# final.net
KiCad netlist of a schematic drawn in EAGLE
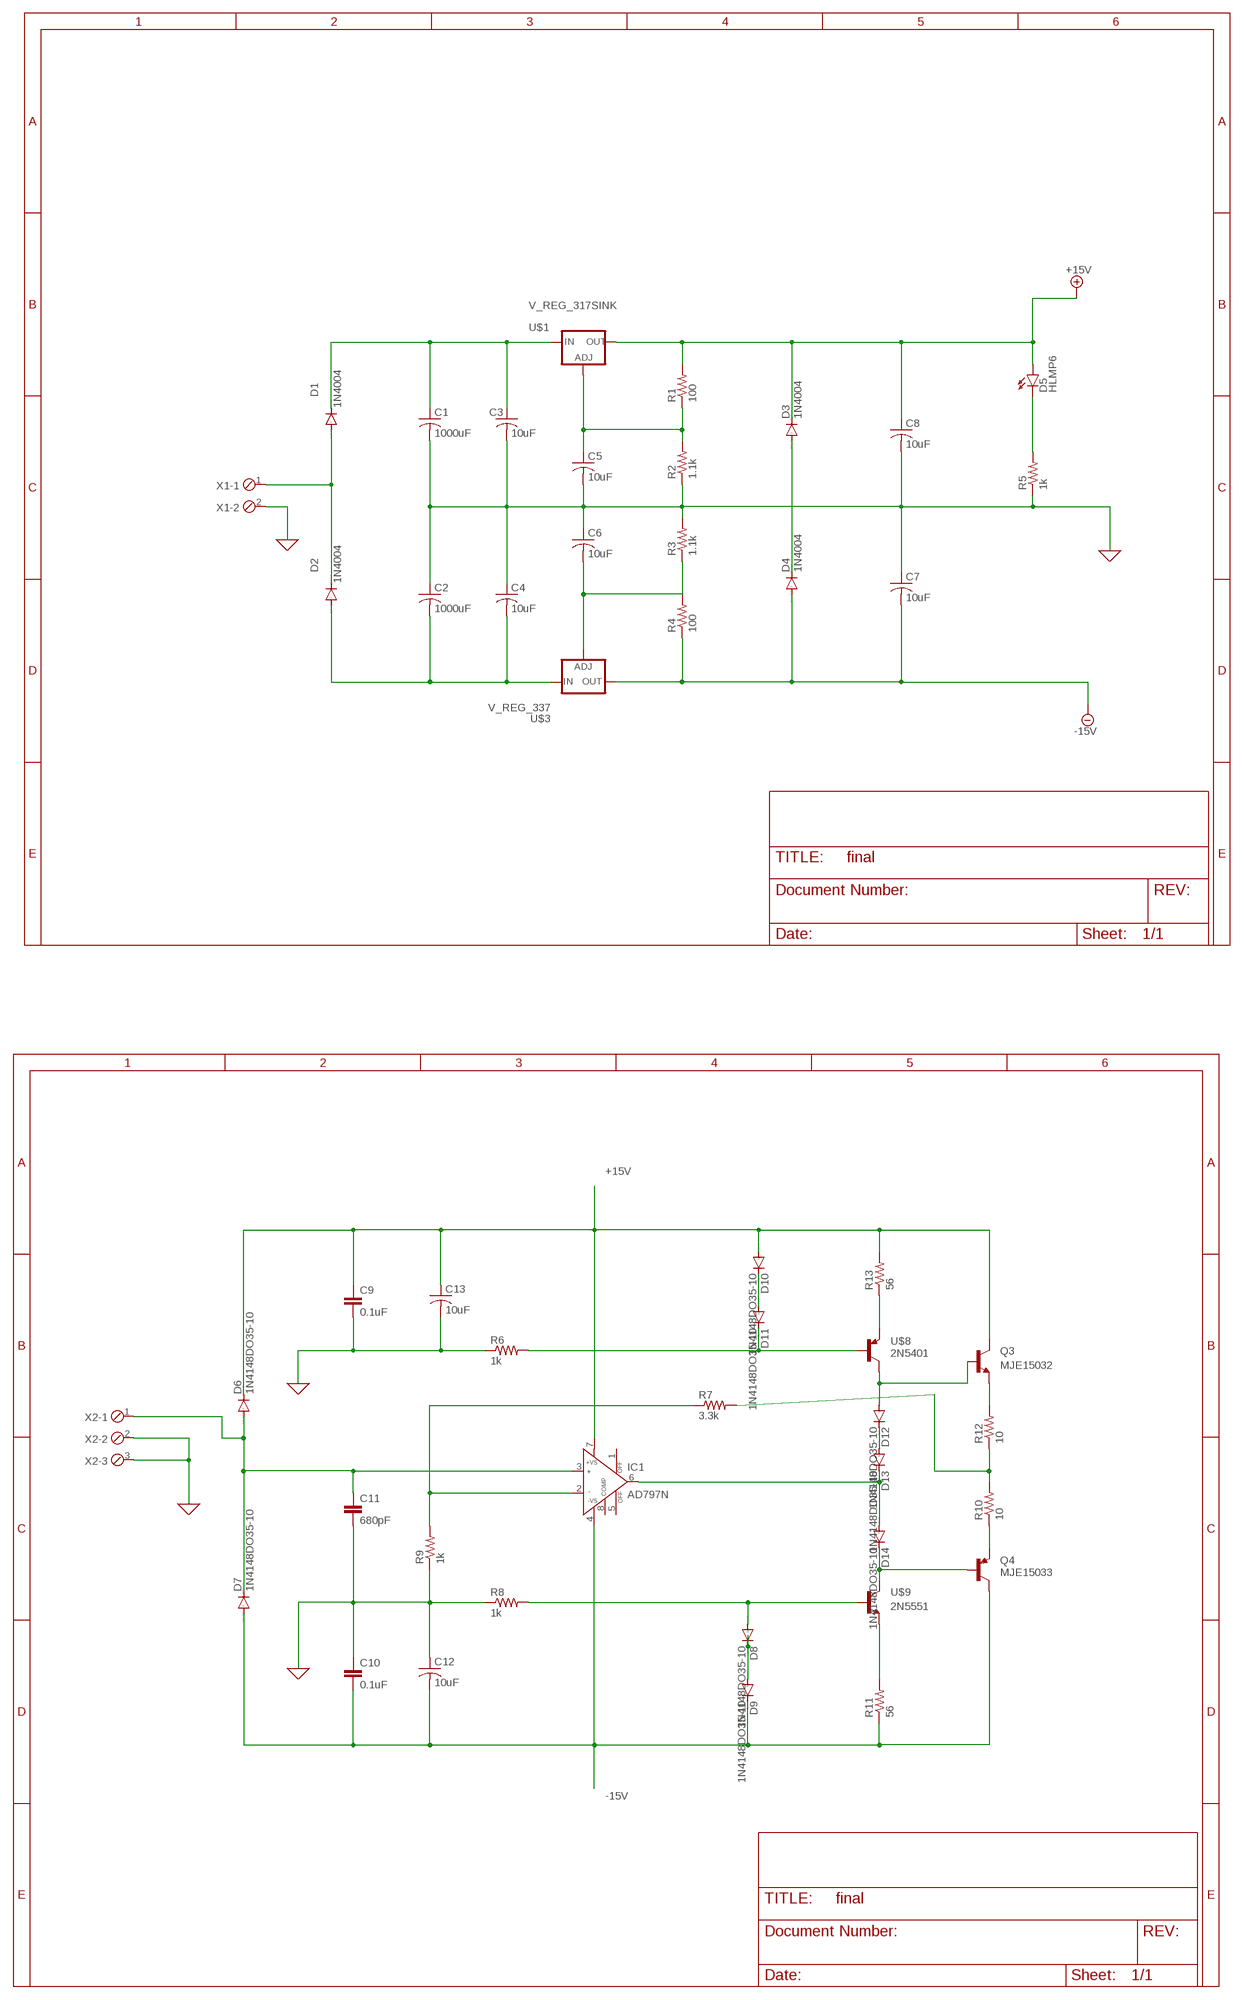
[diagram p0: schematic, sheet 1, part 1 of 2]
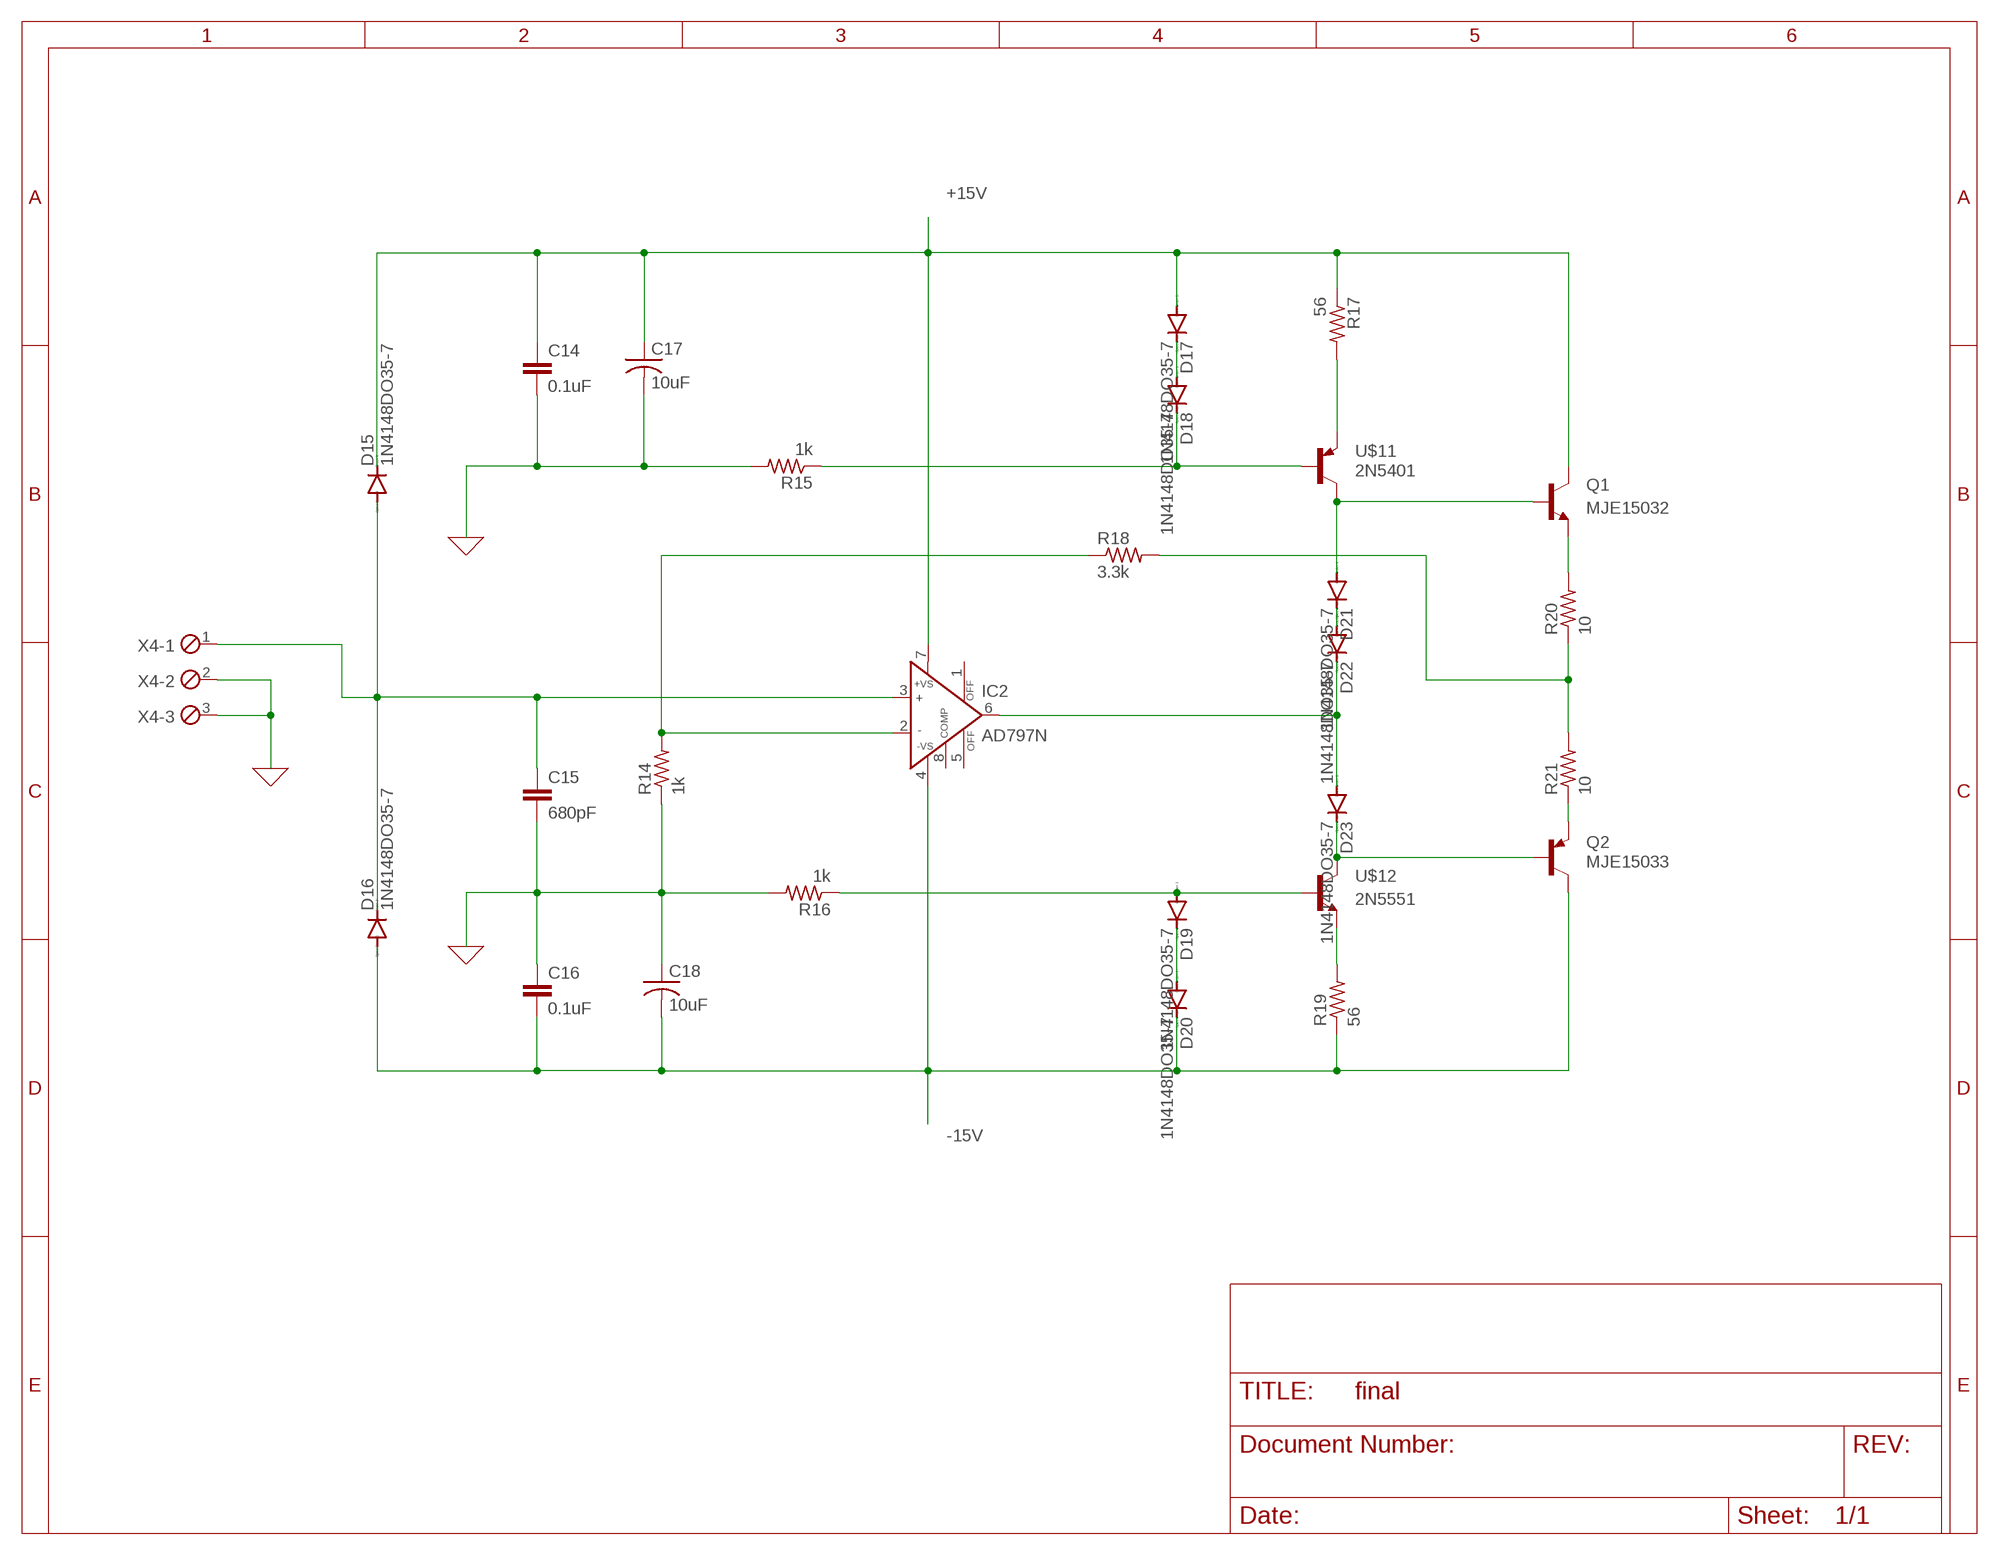
[diagram p1: schematic, sheet 1, part 2 of 2]

(export (version "E")
  (design (tool "Eeschema 10.0.6"))
  (components
    (comp (ref "C1")
      (value "1000uF")
      (footprint "eagle-import:C050-024X044")
      (libsource (lib "eagle-import") (part "C-US050-024X044"))
    )
    (comp (ref "C2")
      (value "1000uF")
      (footprint "eagle-import:C050-024X044")
      (libsource (lib "eagle-import") (part "C-US050-024X044"))
    )
    (comp (ref "C3")
      (value "10uF")
      (footprint "eagle-import:C050-024X044")
      (libsource (lib "eagle-import") (part "C-US050-024X044"))
    )
    (comp (ref "C4")
      (value "10uF")
      (footprint "eagle-import:C050-024X044")
      (libsource (lib "eagle-import") (part "C-US050-024X044"))
    )
    (comp (ref "C5")
      (value "10uF")
      (footprint "eagle-import:C050-024X044")
      (libsource (lib "eagle-import") (part "C-US050-024X044"))
    )
    (comp (ref "C6")
      (value "10uF")
      (footprint "eagle-import:C050-024X044")
      (libsource (lib "eagle-import") (part "C-US050-024X044"))
    )
    (comp (ref "C7")
      (value "10uF")
      (footprint "eagle-import:C050-024X044")
      (libsource (lib "eagle-import") (part "C-US050-024X044"))
    )
    (comp (ref "C8")
      (value "10uF")
      (footprint "eagle-import:C050-024X044")
      (libsource (lib "eagle-import") (part "C-US050-024X044"))
    )
    (comp (ref "C9")
      (value "0.1uF")
      (footprint "eagle-import:C2.5-3")
      (libsource (lib "eagle-import") (part "C2,5-3"))
    )
    (comp (ref "C10")
      (value "0.1uF")
      (footprint "eagle-import:C2.5-3")
      (libsource (lib "eagle-import") (part "C2,5-3"))
    )
    (comp (ref "C11")
      (value "680pF")
      (footprint "eagle-import:C2.5-3")
      (libsource (lib "eagle-import") (part "C2,5-3"))
    )
    (comp (ref "C12")
      (value "10uF")
      (footprint "eagle-import:C050-024X044")
      (libsource (lib "eagle-import") (part "C-US050-024X044"))
    )
    (comp (ref "C13")
      (value "10uF")
      (footprint "eagle-import:C050-024X044")
      (libsource (lib "eagle-import") (part "C-US050-024X044"))
    )
    (comp (ref "C14")
      (value "0.1uF")
      (footprint "eagle-import:C2.5-3")
      (libsource (lib "eagle-import") (part "C2,5-3"))
    )
    (comp (ref "C15")
      (value "680pF")
      (footprint "eagle-import:C2.5-3")
      (libsource (lib "eagle-import") (part "C2,5-3"))
    )
    (comp (ref "C16")
      (value "0.1uF")
      (footprint "eagle-import:C2.5-3")
      (libsource (lib "eagle-import") (part "C2,5-3"))
    )
    (comp (ref "C17")
      (value "10uF")
      (footprint "eagle-import:C050-024X044")
      (libsource (lib "eagle-import") (part "C-US050-024X044"))
    )
    (comp (ref "C18")
      (value "10uF")
      (footprint "eagle-import:C050-024X044")
      (libsource (lib "eagle-import") (part "C-US050-024X044"))
    )
    (comp (ref "D1")
      (value "1N4004")
      (footprint "eagle-import:DO41-10")
      (libsource (lib "eagle-import") (part "1N4004"))
    )
    (comp (ref "D2")
      (value "1N4004")
      (footprint "eagle-import:DO41-10")
      (libsource (lib "eagle-import") (part "1N4004"))
    )
    (comp (ref "D3")
      (value "1N4004")
      (footprint "eagle-import:DO41-10")
      (libsource (lib "eagle-import") (part "1N4004"))
    )
    (comp (ref "D4")
      (value "1N4004")
      (footprint "eagle-import:DO41-10")
      (libsource (lib "eagle-import") (part "1N4004"))
    )
    (comp (ref "D5")
      (value "HLMP6")
      (footprint "eagle-import:HLMP6")
      (fields (field (name "MF") "AGILENT TECHNOLOGIES") (field (name "MPN") "HLMP-6500"))
      (libsource (lib "eagle-import") (part "HLMP6"))
    )
    (comp (ref "D6")
      (value "1N4148DO35-10")
      (footprint "eagle-import:DO35-10")
      (libsource (lib "eagle-import") (part "1N4148DO35-10"))
    )
    (comp (ref "D7")
      (value "1N4148DO35-10")
      (footprint "eagle-import:DO35-10")
      (libsource (lib "eagle-import") (part "1N4148DO35-10"))
    )
    (comp (ref "D8")
      (value "1N4148DO35-10")
      (footprint "eagle-import:DO35-10")
      (libsource (lib "eagle-import") (part "1N4148DO35-10"))
    )
    (comp (ref "D9")
      (value "1N4148DO35-10")
      (footprint "eagle-import:DO35-10")
      (libsource (lib "eagle-import") (part "1N4148DO35-10"))
    )
    (comp (ref "D10")
      (value "1N4148DO35-10")
      (footprint "eagle-import:DO35-10")
      (libsource (lib "eagle-import") (part "1N4148DO35-10"))
    )
    (comp (ref "D11")
      (value "1N4148DO35-10")
      (footprint "eagle-import:DO35-10")
      (libsource (lib "eagle-import") (part "1N4148DO35-10"))
    )
    (comp (ref "D12")
      (value "1N4148DO35-10")
      (footprint "eagle-import:DO35-10")
      (libsource (lib "eagle-import") (part "1N4148DO35-10"))
    )
    (comp (ref "D13")
      (value "1N4148DO35-10")
      (footprint "eagle-import:DO35-10")
      (libsource (lib "eagle-import") (part "1N4148DO35-10"))
    )
    (comp (ref "D14")
      (value "1N4148DO35-10")
      (footprint "eagle-import:DO35-10")
      (libsource (lib "eagle-import") (part "1N4148DO35-10"))
    )
    (comp (ref "D15")
      (value "1N4148DO35-7")
      (footprint "eagle-import:DO35-7")
      (libsource (lib "eagle-import") (part "1N4148DO35-7"))
    )
    (comp (ref "D16")
      (value "1N4148DO35-7")
      (footprint "eagle-import:DO35-7")
      (libsource (lib "eagle-import") (part "1N4148DO35-7"))
    )
    (comp (ref "D17")
      (value "1N4148DO35-7")
      (footprint "eagle-import:DO35-7")
      (libsource (lib "eagle-import") (part "1N4148DO35-7"))
    )
    (comp (ref "D18")
      (value "1N4148DO35-7")
      (footprint "eagle-import:DO35-7")
      (libsource (lib "eagle-import") (part "1N4148DO35-7"))
    )
    (comp (ref "D19")
      (value "1N4148DO35-7")
      (footprint "eagle-import:DO35-7")
      (libsource (lib "eagle-import") (part "1N4148DO35-7"))
    )
    (comp (ref "D20")
      (value "1N4148DO35-7")
      (footprint "eagle-import:DO35-7")
      (libsource (lib "eagle-import") (part "1N4148DO35-7"))
    )
    (comp (ref "D21")
      (value "1N4148DO35-7")
      (footprint "eagle-import:DO35-7")
      (libsource (lib "eagle-import") (part "1N4148DO35-7"))
    )
    (comp (ref "D22")
      (value "1N4148DO35-7")
      (footprint "eagle-import:DO35-7")
      (libsource (lib "eagle-import") (part "1N4148DO35-7"))
    )
    (comp (ref "D23")
      (value "1N4148DO35-7")
      (footprint "eagle-import:DO35-7")
      (libsource (lib "eagle-import") (part "1N4148DO35-7"))
    )
    (comp (ref "IC1")
      (value "AD797N")
      (footprint "eagle-import:DIL08")
      (fields (field (name "MF") "ALTERA CORPORATION") (field (name "MPN") "AD797ANZ"))
      (libsource (lib "eagle-import") (part "AD797N"))
    )
    (comp (ref "IC2")
      (value "AD797N")
      (footprint "eagle-import:DIL08")
      (fields (field (name "MF") "ALTERA CORPORATION") (field (name "MPN") "AD797ANZ"))
      (libsource (lib "eagle-import") (part "AD797N"))
    )
    (comp (ref "Q1")
      (value "MJE15032")
      (footprint "eagle-import:TO220V")
      (libsource (lib "eagle-import") (part "MJE15032"))
    )
    (comp (ref "Q2")
      (value "MJE15033")
      (footprint "eagle-import:TO220V")
      (libsource (lib "eagle-import") (part "MJE15033"))
    )
    (comp (ref "Q3")
      (value "MJE15032")
      (footprint "eagle-import:TO220V")
      (libsource (lib "eagle-import") (part "MJE15032"))
    )
    (comp (ref "Q4")
      (value "MJE15033")
      (footprint "eagle-import:TO220V")
      (libsource (lib "eagle-import") (part "MJE15033"))
    )
    (comp (ref "R1")
      (value "100")
      (footprint "eagle-import:0204_7")
      (libsource (lib "eagle-import") (part "R-US_0204/7"))
    )
    (comp (ref "R2")
      (value "1.1k")
      (footprint "eagle-import:0204_7")
      (libsource (lib "eagle-import") (part "R-US_0204/7"))
    )
    (comp (ref "R3")
      (value "1.1k")
      (footprint "eagle-import:0204_7")
      (libsource (lib "eagle-import") (part "R-US_0204/7"))
    )
    (comp (ref "R4")
      (value "100")
      (footprint "eagle-import:0204_7")
      (libsource (lib "eagle-import") (part "R-US_0204/7"))
    )
    (comp (ref "R5")
      (value "1k")
      (footprint "eagle-import:0204_7")
      (libsource (lib "eagle-import") (part "R-US_0204/7"))
    )
    (comp (ref "R6")
      (value "1k")
      (footprint "eagle-import:0204_7")
      (libsource (lib "eagle-import") (part "R-US_0204/7"))
    )
    (comp (ref "R7")
      (value "3.3k")
      (footprint "eagle-import:0204_7")
      (libsource (lib "eagle-import") (part "R-US_0204/7"))
    )
    (comp (ref "R8")
      (value "1k")
      (footprint "eagle-import:0204_7")
      (libsource (lib "eagle-import") (part "R-US_0204/7"))
    )
    (comp (ref "R9")
      (value "1k")
      (footprint "eagle-import:0204_7")
      (libsource (lib "eagle-import") (part "R-US_0204/7"))
    )
    (comp (ref "R10")
      (value "10")
      (footprint "eagle-import:0204_7")
      (libsource (lib "eagle-import") (part "R-US_0204/7"))
    )
    (comp (ref "R11")
      (value "56")
      (footprint "eagle-import:0204_7")
      (libsource (lib "eagle-import") (part "R-US_0204/7"))
    )
    (comp (ref "R12")
      (value "10")
      (footprint "eagle-import:0204_7")
      (libsource (lib "eagle-import") (part "R-US_0204/7"))
    )
    (comp (ref "R13")
      (value "56")
      (footprint "eagle-import:0204_7")
      (libsource (lib "eagle-import") (part "R-US_0204/7"))
    )
    (comp (ref "R14")
      (value "1k")
      (footprint "eagle-import:0204_7")
      (libsource (lib "eagle-import") (part "R-US_0204/7"))
    )
    (comp (ref "R15")
      (value "1k")
      (footprint "eagle-import:0204_7")
      (libsource (lib "eagle-import") (part "R-US_0204/7"))
    )
    (comp (ref "R16")
      (value "1k")
      (footprint "eagle-import:0204_7")
      (libsource (lib "eagle-import") (part "R-US_0204/7"))
    )
    (comp (ref "R17")
      (value "56")
      (footprint "eagle-import:0204_7")
      (libsource (lib "eagle-import") (part "R-US_0204/7"))
    )
    (comp (ref "R18")
      (value "3.3k")
      (footprint "eagle-import:0204_7")
      (libsource (lib "eagle-import") (part "R-US_0204/7"))
    )
    (comp (ref "R19")
      (value "56")
      (footprint "eagle-import:0204_7")
      (libsource (lib "eagle-import") (part "R-US_0204/7"))
    )
    (comp (ref "R20")
      (value "10")
      (footprint "eagle-import:0204_7")
      (libsource (lib "eagle-import") (part "R-US_0204/7"))
    )
    (comp (ref "R21")
      (value "10")
      (footprint "eagle-import:0204_7")
      (libsource (lib "eagle-import") (part "R-US_0204/7"))
    )
    (comp (ref "U$1")
      (value "V_REG_317SINK")
      (footprint "eagle-import:TO220-ADJ")
      (libsource (lib "eagle-import") (part "V_REG_317SINK"))
    )
    (comp (ref "U$3")
      (value "V_REG_337")
      (footprint "eagle-import:TO220-ADJ-NEG")
      (libsource (lib "eagle-import") (part "V_REG_337"))
    )
    (comp (ref "U$8")
      (value "2N5401")
      (footprint "eagle-import:2N5401")
      (libsource (lib "eagle-import") (part "2N5401"))
    )
    (comp (ref "U$9")
      (value "2N5551")
      (footprint "eagle-import:2N5551")
      (libsource (lib "eagle-import") (part "2N5551"))
    )
    (comp (ref "U$11")
      (value "2N5401")
      (footprint "eagle-import:2N5401")
      (libsource (lib "eagle-import") (part "2N5401"))
    )
    (comp (ref "U$12")
      (value "2N5551")
      (footprint "eagle-import:2N5551")
      (libsource (lib "eagle-import") (part "2N5551"))
    )
    (comp (ref "X1")
      (value "MPT2")
      (footprint "eagle-import:2POL254")
      (libsource (lib "eagle-import") (part "MPT2"))
    )
    (comp (ref "X2")
      (value "MPT3")
      (footprint "eagle-import:3POL254")
      (libsource (lib "eagle-import") (part "MPT3"))
    )
    (comp (ref "X4")
      (value "MPT3")
      (footprint "eagle-import:3POL254")
      (libsource (lib "eagle-import") (part "MPT3"))
    )
  )
  (nets
    (net (code "1") (name "+15V") (class "Default")
      (node (ref "C13") (pin "1") (pinfunction "1_1") (pintype "passive"))
      (node (ref "C14") (pin "1") (pinfunction "1_1") (pintype "passive"))
      (node (ref "C17") (pin "1") (pinfunction "1_1") (pintype "passive"))
      (node (ref "C8") (pin "1") (pinfunction "1_1") (pintype "passive"))
      (node (ref "C9") (pin "1") (pinfunction "1_1") (pintype "passive"))
      (node (ref "D10") (pin "A") (pinfunction "A_A") (pintype "passive"))
      (node (ref "D15") (pin "C") (pinfunction "C_C") (pintype "passive"))
      (node (ref "D17") (pin "A") (pinfunction "A_A") (pintype "passive"))
      (node (ref "D3") (pin "C") (pinfunction "C_C") (pintype "passive"))
      (node (ref "D5") (pin "A") (pinfunction "A_A") (pintype "passive"))
      (node (ref "D6") (pin "C") (pinfunction "C_C") (pintype "passive"))
      (node (ref "IC1") (pin "7") (pinfunction "+VS_7") (pintype "input"))
      (node (ref "IC2") (pin "7") (pinfunction "+VS_7") (pintype "input"))
      (node (ref "Q1") (pin "2") (pinfunction "C_2") (pintype "passive"))
      (node (ref "Q3") (pin "2") (pinfunction "C_2") (pintype "passive"))
      (node (ref "R1") (pin "2") (pinfunction "2_2") (pintype "passive"))
      (node (ref "R13") (pin "2") (pinfunction "2_2") (pintype "passive"))
      (node (ref "R17") (pin "1") (pinfunction "1_1") (pintype "passive"))
      (node (ref "U$1") (pin "OUT") (pinfunction "OUT_OUT") (pintype "output"))
    )
    (net (code "2") (name "-15V") (class "Default")
      (node (ref "C10") (pin "2") (pinfunction "2_2") (pintype "passive"))
      (node (ref "C12") (pin "2") (pinfunction "2_2") (pintype "passive"))
      (node (ref "C16") (pin "2") (pinfunction "2_2") (pintype "passive"))
      (node (ref "C18") (pin "2") (pinfunction "2_2") (pintype "passive"))
      (node (ref "C7") (pin "2") (pinfunction "2_2") (pintype "passive"))
      (node (ref "D16") (pin "A") (pinfunction "A_A") (pintype "passive"))
      (node (ref "D20") (pin "C") (pinfunction "C_C") (pintype "passive"))
      (node (ref "D4") (pin "A") (pinfunction "A_A") (pintype "passive"))
      (node (ref "D7") (pin "A") (pinfunction "A_A") (pintype "passive"))
      (node (ref "D9") (pin "C") (pinfunction "C_C") (pintype "passive"))
      (node (ref "IC1") (pin "4") (pinfunction "-VS_4") (pintype "input"))
      (node (ref "IC2") (pin "4") (pinfunction "-VS_4") (pintype "input"))
      (node (ref "Q2") (pin "2") (pinfunction "C_2") (pintype "passive"))
      (node (ref "Q4") (pin "2") (pinfunction "C_2") (pintype "passive"))
      (node (ref "R11") (pin "1") (pinfunction "1_1") (pintype "passive"))
      (node (ref "R19") (pin "1") (pinfunction "1_1") (pintype "passive"))
      (node (ref "R4") (pin "1") (pinfunction "1_1") (pintype "passive"))
      (node (ref "U$3") (pin "OUT") (pinfunction "OUT_OUT") (pintype "output"))
    )
    (net (code "3") (name "GND") (class "Default")
      (node (ref "C1") (pin "2") (pinfunction "2_2") (pintype "passive"))
      (node (ref "C10") (pin "1") (pinfunction "1_1") (pintype "passive"))
      (node (ref "C11") (pin "2") (pinfunction "2_2") (pintype "passive"))
      (node (ref "C12") (pin "1") (pinfunction "1_1") (pintype "passive"))
      (node (ref "C13") (pin "2") (pinfunction "2_2") (pintype "passive"))
      (node (ref "C14") (pin "2") (pinfunction "2_2") (pintype "passive"))
      (node (ref "C15") (pin "2") (pinfunction "2_2") (pintype "passive"))
      (node (ref "C16") (pin "1") (pinfunction "1_1") (pintype "passive"))
      (node (ref "C17") (pin "2") (pinfunction "2_2") (pintype "passive"))
      (node (ref "C18") (pin "1") (pinfunction "1_1") (pintype "passive"))
      (node (ref "C2") (pin "1") (pinfunction "1_1") (pintype "passive"))
      (node (ref "C3") (pin "2") (pinfunction "2_2") (pintype "passive"))
      (node (ref "C4") (pin "1") (pinfunction "1_1") (pintype "passive"))
      (node (ref "C5") (pin "2") (pinfunction "2_2") (pintype "passive"))
      (node (ref "C6") (pin "1") (pinfunction "1_1") (pintype "passive"))
      (node (ref "C7") (pin "1") (pinfunction "1_1") (pintype "passive"))
      (node (ref "C8") (pin "2") (pinfunction "2_2") (pintype "passive"))
      (node (ref "C9") (pin "2") (pinfunction "2_2") (pintype "passive"))
      (node (ref "R14") (pin "1") (pinfunction "1_1") (pintype "passive"))
      (node (ref "R15") (pin "2") (pinfunction "2_2") (pintype "passive"))
      (node (ref "R16") (pin "2") (pinfunction "2_2") (pintype "passive"))
      (node (ref "R2") (pin "1") (pinfunction "1_1") (pintype "passive"))
      (node (ref "R3") (pin "2") (pinfunction "2_2") (pintype "passive"))
      (node (ref "R5") (pin "1") (pinfunction "1_1") (pintype "passive"))
      (node (ref "R6") (pin "1") (pinfunction "1_1") (pintype "passive"))
      (node (ref "R8") (pin "1") (pinfunction "1_1") (pintype "passive"))
      (node (ref "R9") (pin "1") (pinfunction "1_1") (pintype "passive"))
      (node (ref "X1") (pin "2") (pinfunction "1_2") (pintype "passive"))
      (node (ref "X2") (pin "2") (pinfunction "1_2") (pintype "passive"))
      (node (ref "X2") (pin "3") (pinfunction "1_3") (pintype "passive"))
      (node (ref "X4") (pin "2") (pinfunction "1_2") (pintype "passive"))
      (node (ref "X4") (pin "3") (pinfunction "1_3") (pintype "passive"))
    )
    (net (code "4") (name "Net-(C1-Pad1)") (class "Default")
      (node (ref "C1") (pin "1") (pinfunction "1_1") (pintype "passive"))
      (node (ref "C3") (pin "1") (pinfunction "1_1") (pintype "passive"))
      (node (ref "D1") (pin "C") (pinfunction "C_C") (pintype "passive"))
      (node (ref "U$1") (pin "IN") (pinfunction "IN_IN") (pintype "input"))
    )
    (net (code "5") (name "Net-(C2-Pad2)") (class "Default")
      (node (ref "C2") (pin "2") (pinfunction "2_2") (pintype "passive"))
      (node (ref "C4") (pin "2") (pinfunction "2_2") (pintype "passive"))
      (node (ref "D2") (pin "A") (pinfunction "A_A") (pintype "passive"))
      (node (ref "U$3") (pin "IN") (pinfunction "IN_IN") (pintype "input"))
    )
    (net (code "6") (name "Net-(C5-Pad1)") (class "Default")
      (node (ref "C5") (pin "1") (pinfunction "1_1") (pintype "passive"))
      (node (ref "R1") (pin "1") (pinfunction "1_1") (pintype "passive"))
      (node (ref "R2") (pin "2") (pinfunction "2_2") (pintype "passive"))
      (node (ref "U$1") (pin "ADJ") (pinfunction "ADJ_ADJ") (pintype "input"))
    )
    (net (code "7") (name "Net-(C6-Pad2)") (class "Default")
      (node (ref "C6") (pin "2") (pinfunction "2_2") (pintype "passive"))
      (node (ref "R3") (pin "1") (pinfunction "1_1") (pintype "passive"))
      (node (ref "R4") (pin "2") (pinfunction "2_2") (pintype "passive"))
      (node (ref "U$3") (pin "ADJ") (pinfunction "ADJ_ADJ") (pintype "input"))
    )
    (net (code "8") (name "Net-(D1-PadA)") (class "Default")
      (node (ref "D1") (pin "A") (pinfunction "A_A") (pintype "passive"))
      (node (ref "D2") (pin "C") (pinfunction "C_C") (pintype "passive"))
      (node (ref "X1") (pin "1") (pinfunction "1_1") (pintype "passive"))
    )
    (net (code "9") (name "Net-(D3-PadA)") (class "Default")
      (node (ref "D3") (pin "A") (pinfunction "A_A") (pintype "passive"))
      (node (ref "D4") (pin "C") (pinfunction "C_C") (pintype "passive"))
    )
    (net (code "10") (name "Net-(D5-PadK)") (class "Default")
      (node (ref "D5") (pin "K") (pinfunction "K_K") (pintype "passive"))
      (node (ref "R5") (pin "2") (pinfunction "2_2") (pintype "passive"))
    )
    (net (code "11") (name "Net-(D8-PadA)") (class "Default")
      (node (ref "D8") (pin "A") (pinfunction "A_A") (pintype "passive"))
      (node (ref "R8") (pin "2") (pinfunction "2_2") (pintype "passive"))
      (node (ref "U$9") (pin "B") (pinfunction "B_B") (pintype "passive"))
    )
    (net (code "12") (name "Net-(D8-PadC)") (class "Default")
      (node (ref "D8") (pin "C") (pinfunction "C_C") (pintype "passive"))
      (node (ref "D9") (pin "A") (pinfunction "A_A") (pintype "passive"))
    )
    (net (code "13") (name "Net-(D10-PadC)") (class "Default")
      (node (ref "D10") (pin "C") (pinfunction "C_C") (pintype "passive"))
      (node (ref "D11") (pin "A") (pinfunction "A_A") (pintype "passive"))
    )
    (net (code "14") (name "Net-(D11-PadC)") (class "Default")
      (node (ref "D11") (pin "C") (pinfunction "C_C") (pintype "passive"))
      (node (ref "R6") (pin "2") (pinfunction "2_2") (pintype "passive"))
      (node (ref "U$8") (pin "B") (pinfunction "B_B") (pintype "passive"))
    )
    (net (code "15") (name "Net-(D12-PadC)") (class "Default")
      (node (ref "D12") (pin "C") (pinfunction "C_C") (pintype "passive"))
      (node (ref "D13") (pin "A") (pinfunction "A_A") (pintype "passive"))
    )
    (net (code "16") (name "Net-(D17-PadC)") (class "Default")
      (node (ref "D17") (pin "C") (pinfunction "C_C") (pintype "passive"))
      (node (ref "D18") (pin "A") (pinfunction "A_A") (pintype "passive"))
    )
    (net (code "17") (name "Net-(D18-PadC)") (class "Default")
      (node (ref "D18") (pin "C") (pinfunction "C_C") (pintype "passive"))
      (node (ref "R15") (pin "1") (pinfunction "1_1") (pintype "passive"))
      (node (ref "U$11") (pin "B") (pinfunction "B_B") (pintype "passive"))
    )
    (net (code "18") (name "Net-(D19-PadA)") (class "Default")
      (node (ref "D19") (pin "A") (pinfunction "A_A") (pintype "passive"))
      (node (ref "R16") (pin "1") (pinfunction "1_1") (pintype "passive"))
      (node (ref "U$12") (pin "B") (pinfunction "B_B") (pintype "passive"))
    )
    (net (code "19") (name "Net-(D19-PadC)") (class "Default")
      (node (ref "D19") (pin "C") (pinfunction "C_C") (pintype "passive"))
      (node (ref "D20") (pin "A") (pinfunction "A_A") (pintype "passive"))
    )
    (net (code "20") (name "Net-(D21-PadC)") (class "Default")
      (node (ref "D21") (pin "C") (pinfunction "C_C") (pintype "passive"))
      (node (ref "D22") (pin "A") (pinfunction "A_A") (pintype "passive"))
    )
    (net (code "21") (name "Net-(IC1-IN+)") (class "Default")
      (node (ref "C11") (pin "1") (pinfunction "1_1") (pintype "passive"))
      (node (ref "D6") (pin "A") (pinfunction "A_A") (pintype "passive"))
      (node (ref "D7") (pin "C") (pinfunction "C_C") (pintype "passive"))
      (node (ref "IC1") (pin "3") (pinfunction "IN+_3") (pintype "input"))
      (node (ref "X2") (pin "1") (pinfunction "1_1") (pintype "passive"))
    )
    (net (code "22") (name "Net-(IC1-IN-)") (class "Default")
      (node (ref "IC1") (pin "2") (pinfunction "IN-_2") (pintype "input"))
      (node (ref "R7") (pin "1") (pinfunction "1_1") (pintype "passive"))
      (node (ref "R9") (pin "2") (pinfunction "2_2") (pintype "passive"))
    )
    (net (code "23") (name "Net-(IC1-OUT)") (class "Default")
      (node (ref "D13") (pin "C") (pinfunction "C_C") (pintype "passive"))
      (node (ref "D14") (pin "A") (pinfunction "A_A") (pintype "passive"))
      (node (ref "IC1") (pin "6") (pinfunction "OUT_6") (pintype "output"))
    )
    (net (code "24") (name "Net-(IC2-IN+)") (class "Default")
      (node (ref "C15") (pin "1") (pinfunction "1_1") (pintype "passive"))
      (node (ref "D15") (pin "A") (pinfunction "A_A") (pintype "passive"))
      (node (ref "D16") (pin "C") (pinfunction "C_C") (pintype "passive"))
      (node (ref "IC2") (pin "3") (pinfunction "IN+_3") (pintype "input"))
      (node (ref "X4") (pin "1") (pinfunction "1_1") (pintype "passive"))
    )
    (net (code "25") (name "Net-(IC2-IN-)") (class "Default")
      (node (ref "IC2") (pin "2") (pinfunction "IN-_2") (pintype "input"))
      (node (ref "R14") (pin "2") (pinfunction "2_2") (pintype "passive"))
      (node (ref "R18") (pin "1") (pinfunction "1_1") (pintype "passive"))
    )
    (net (code "26") (name "Net-(IC2-OUT)") (class "Default")
      (node (ref "D22") (pin "C") (pinfunction "C_C") (pintype "passive"))
      (node (ref "D23") (pin "A") (pinfunction "A_A") (pintype "passive"))
      (node (ref "IC2") (pin "6") (pinfunction "OUT_6") (pintype "output"))
    )
    (net (code "27") (name "Net-(Q1-B)") (class "Default")
      (node (ref "D21") (pin "A") (pinfunction "A_A") (pintype "passive"))
      (node (ref "Q1") (pin "1") (pinfunction "B_1") (pintype "passive"))
      (node (ref "U$11") (pin "E") (pinfunction "C_E") (pintype "passive"))
    )
    (net (code "28") (name "Net-(Q1-E)") (class "Default")
      (node (ref "Q1") (pin "3") (pinfunction "E_3") (pintype "passive"))
      (node (ref "R20") (pin "2") (pinfunction "2_2") (pintype "passive"))
    )
    (net (code "29") (name "Net-(Q2-B)") (class "Default")
      (node (ref "D23") (pin "C") (pinfunction "C_C") (pintype "passive"))
      (node (ref "Q2") (pin "1") (pinfunction "B_1") (pintype "passive"))
      (node (ref "U$12") (pin "C") (pinfunction "C_C") (pintype "passive"))
    )
    (net (code "30") (name "Net-(Q2-E)") (class "Default")
      (node (ref "Q2") (pin "3") (pinfunction "E_3") (pintype "passive"))
      (node (ref "R21") (pin "1") (pinfunction "1_1") (pintype "passive"))
    )
    (net (code "31") (name "Net-(Q3-B)") (class "Default")
      (node (ref "D12") (pin "A") (pinfunction "A_A") (pintype "passive"))
      (node (ref "Q3") (pin "1") (pinfunction "B_1") (pintype "passive"))
      (node (ref "U$8") (pin "E") (pinfunction "C_E") (pintype "passive"))
    )
    (net (code "32") (name "Net-(Q3-E)") (class "Default")
      (node (ref "Q3") (pin "3") (pinfunction "E_3") (pintype "passive"))
      (node (ref "R12") (pin "2") (pinfunction "2_2") (pintype "passive"))
    )
    (net (code "33") (name "Net-(Q4-B)") (class "Default")
      (node (ref "D14") (pin "C") (pinfunction "C_C") (pintype "passive"))
      (node (ref "Q4") (pin "1") (pinfunction "B_1") (pintype "passive"))
      (node (ref "U$9") (pin "C") (pinfunction "C_C") (pintype "passive"))
    )
    (net (code "34") (name "Net-(Q4-E)") (class "Default")
      (node (ref "Q4") (pin "3") (pinfunction "E_3") (pintype "passive"))
      (node (ref "R10") (pin "1") (pinfunction "1_1") (pintype "passive"))
    )
    (net (code "35") (name "Net-(R10-Pad2)") (class "Default")
      (node (ref "R10") (pin "2") (pinfunction "2_2") (pintype "passive"))
      (node (ref "R12") (pin "1") (pinfunction "1_1") (pintype "passive"))
      (node (ref "R7") (pin "2") (pinfunction "2_2") (pintype "passive"))
    )
    (net (code "36") (name "Net-(R11-Pad2)") (class "Default")
      (node (ref "R11") (pin "2") (pinfunction "2_2") (pintype "passive"))
      (node (ref "U$9") (pin "E") (pinfunction "E_E") (pintype "passive"))
    )
    (net (code "37") (name "Net-(R18-Pad2)") (class "Default")
      (node (ref "R18") (pin "2") (pinfunction "2_2") (pintype "passive"))
      (node (ref "R20") (pin "1") (pinfunction "1_1") (pintype "passive"))
      (node (ref "R21") (pin "2") (pinfunction "2_2") (pintype "passive"))
    )
    (net (code "38") (name "Net-(R19-Pad2)") (class "Default")
      (node (ref "R19") (pin "2") (pinfunction "2_2") (pintype "passive"))
      (node (ref "U$12") (pin "E") (pinfunction "E_E") (pintype "passive"))
    )
    (net (code "39") (name "Net-(U$8-E)") (class "Default")
      (node (ref "R13") (pin "1") (pinfunction "1_1") (pintype "passive"))
      (node (ref "U$8") (pin "C") (pinfunction "E_C") (pintype "passive"))
    )
    (net (code "40") (name "Net-(U$11-E)") (class "Default")
      (node (ref "R17") (pin "2") (pinfunction "2_2") (pintype "passive"))
      (node (ref "U$11") (pin "C") (pinfunction "E_C") (pintype "passive"))
    )
    (net (code "41") (name "unconnected-(IC1-COMP-Pad8)") (class "Default")
      (node (ref "IC1") (pin "8") (pinfunction "COMP_8") (pintype "passive"))
    )
    (net (code "42") (name "unconnected-(IC1-OFF-Pad1)") (class "Default")
      (node (ref "IC1") (pin "1") (pinfunction "OFF_1") (pintype "passive"))
    )
    (net (code "43") (name "unconnected-(IC1-OFF-Pad5)") (class "Default")
      (node (ref "IC1") (pin "5") (pinfunction "OFF_5") (pintype "passive"))
    )
    (net (code "44") (name "unconnected-(IC2-COMP-Pad8)") (class "Default")
      (node (ref "IC2") (pin "8") (pinfunction "COMP_8") (pintype "passive"))
    )
    (net (code "45") (name "unconnected-(IC2-OFF-Pad1)") (class "Default")
      (node (ref "IC2") (pin "1") (pinfunction "OFF_1") (pintype "passive"))
    )
    (net (code "46") (name "unconnected-(IC2-OFF-Pad5)") (class "Default")
      (node (ref "IC2") (pin "5") (pinfunction "OFF_5") (pintype "passive"))
    )
  )
)
